# DFN1X1_2.net
KiCad netlist of a schematic drawn in Altium Designer
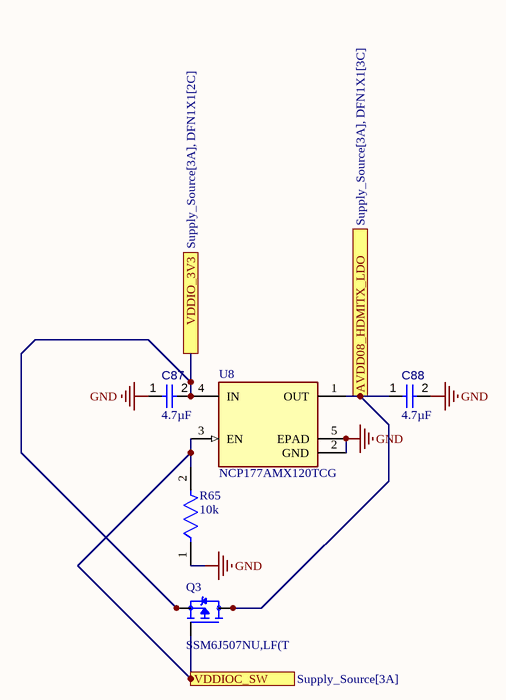
[diagram p0: DFN1X1_2.SchDoc]

(export (version "E")
  (design (tool "Eeschema 10.0.6"))
  (components
    (comp (ref "C87")
      (value "4.7µF")
      (footprint "CAPC0603(1608)100_L")
      (description "Chip Capacitor, 4.7µF +/-20%, 10V, 0603, Thickness 1 mm")
      (fields (field (name "TOLERANCE") "10%") (field (name "Comment") "Capacitor 4.7µF +/-20% 10V 0603"))
      (libsource (lib "MIGUEL ANGEL ALVAREZ GUZMAN") (part "CAP-NP-2"))
    )
    (comp (ref "C88")
      (value "4.7µF")
      (footprint "CAPC0603(1608)100_L")
      (description "Chip Capacitor, 4.7µF +/-20%, 10V, 0603, Thickness 1 mm")
      (fields (field (name "TOLERANCE") "10%") (field (name "Comment") "Capacitor 4.7µF +/-20% 10V 0603"))
      (libsource (lib "MIGUEL ANGEL ALVAREZ GUZMAN") (part "CAP-NP-2"))
    )
    (comp (ref "Q3")
      (value "SSM6J507NU,LF(T")
      (footprint "TRANS_SSM6J507NU,LF(T")
      (description "P-Channel 30V 10A (Ta) 1.25W (Ta) Surface Mount 6-UDFNB (2x2)")
      (libsource (lib "MIGUEL ANGEL ALVAREZ GUZMAN") (part "SSM6J507NU,LF(T"))
    )
    (comp (ref "R65")
      (value "10k")
      (footprint "FP-RT0201-IPC_C")
      (description "Fixed Resistor, Thin Film, 0.05W, 10000ohm, 25V, 0.1% +/-Tol, 50ppm/Cel, Surface Mount, 0201")
      (fields (field (name "TOLERANCE") "0.1%") (field (name "Comment") "RT0201BRE0710KL"))
      (libsource (lib "MIGUEL ANGEL ALVAREZ GUZMAN") (part "1029c3af85768c4190bb7ad29bc67b5"))
    )
    (comp (ref "U8")
      (value "NCP177AMX120TCG")
      (footprint "FP-711AJ-MFG")
      (description "IC REG LINEAR 1.2V 500MA 4XDFN")
      (fields
        (field (name "OCTOPART") "https://octopart.com/ncp177amx120tcg-on+semiconductor-67320276")
        (field (name "MANUFACTURER") "ON Semiconductor")
      )
      (libsource (lib "Altium Content Vault") (part "8ad8dfd97c3e3b1b30caf0b800727eb"))
    )
  )
  (nets
    (net (code "1") (name "/AVDD08_HDMITX_LDO") (class "Default")
      (node (ref "C88") (pin "1") (pinfunction "1_1") (pintype "passive"))
      (node (ref "Q3") (pin "1") (pinfunction "D_1") (pintype "passive"))
      (node (ref "Q3") (pin "2") (pinfunction "D_2") (pintype "passive"))
      (node (ref "Q3") (pin "5") (pinfunction "D_5") (pintype "passive"))
      (node (ref "Q3") (pin "6") (pinfunction "D_6") (pintype "passive"))
      (node (ref "Q3") (pin "7") (pinfunction "D_7") (pintype "passive"))
      (node (ref "U8") (pin "1") (pinfunction "OUT_1") (pintype "power_in"))
    )
    (net (code "2") (name "/VDDIOC_SW") (class "Default")
      (node (ref "Q3") (pin "3") (pinfunction "G_3") (pintype "passive"))
      (node (ref "R65") (pin "2") (pinfunction "2_2") (pintype "passive"))
      (node (ref "U8") (pin "3") (pinfunction "EN_3") (pintype "input"))
    )
    (net (code "3") (name "/VDDIO_3V3") (class "Default")
      (node (ref "C87") (pin "2") (pinfunction "2_2") (pintype "passive"))
      (node (ref "Q3") (pin "4") (pinfunction "S_4") (pintype "passive"))
      (node (ref "Q3") (pin "8") (pinfunction "S_8") (pintype "passive"))
      (node (ref "U8") (pin "4") (pinfunction "IN_4") (pintype "power_in"))
    )
    (net (code "4") (name "GND") (class "Default")
      (node (ref "C87") (pin "1") (pinfunction "1_1") (pintype "passive"))
      (node (ref "C88") (pin "2") (pinfunction "2_2") (pintype "passive"))
      (node (ref "R65") (pin "1") (pinfunction "1_1") (pintype "passive"))
      (node (ref "U8") (pin "2") (pinfunction "GND_2") (pintype "power_in"))
      (node (ref "U8") (pin "5") (pinfunction "EPAD_5") (pintype "power_in"))
    )
  )
)
